# openSX70_ALADDIN_V396SEEED_20180210.net
KiCad netlist of a schematic drawn in EAGLE
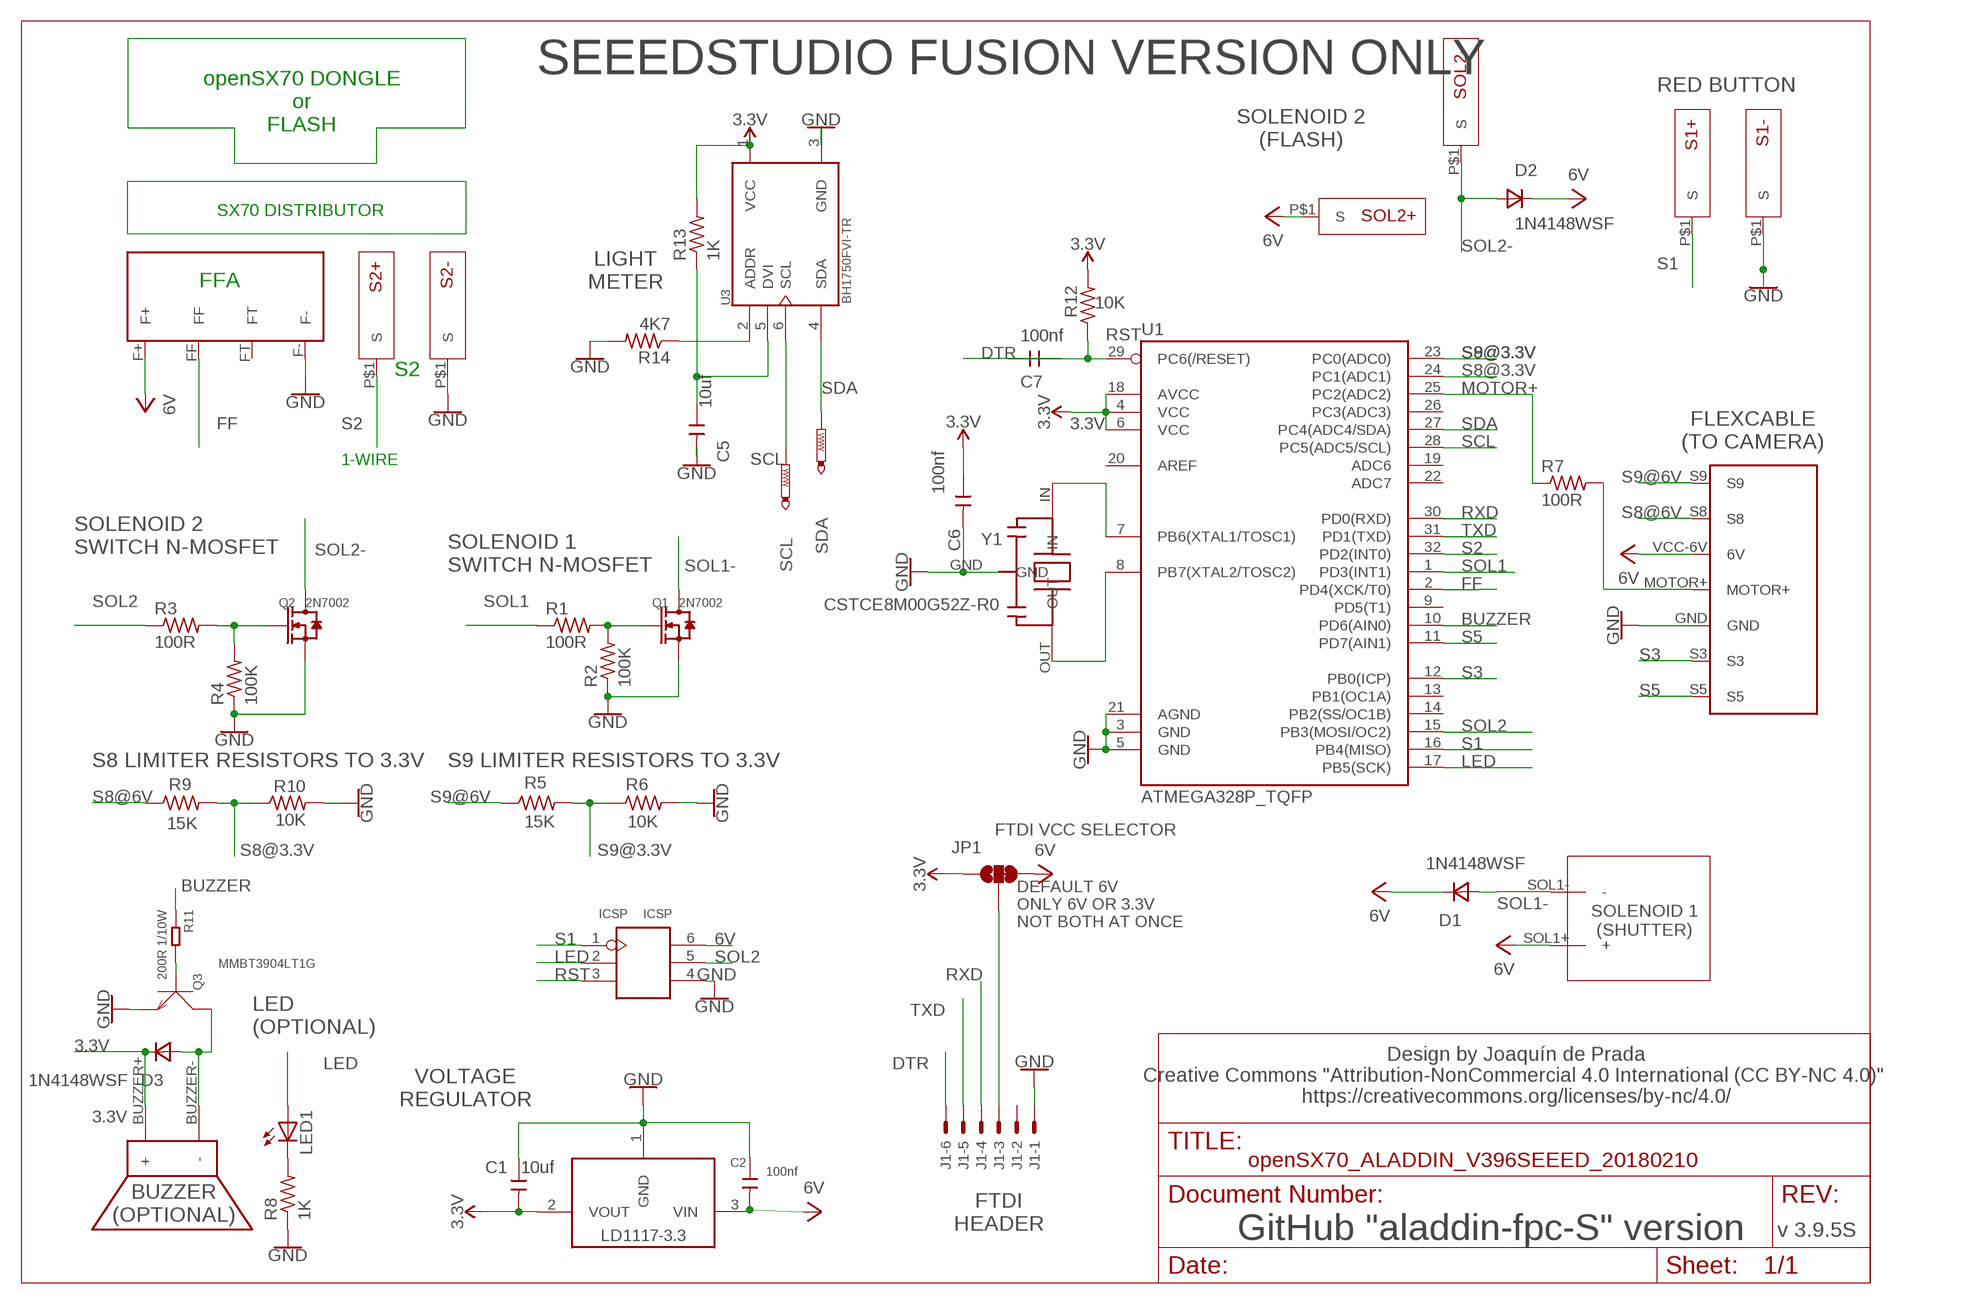
[diagram p0: schematic, sheet 1]

(export (version "E")
  (design (tool "Eeschema 10.0.6"))
  (components
    (comp (ref "C1")
      (value "10uf")
      (footprint "eagle-import:C0603")
      (fields (field (name "MPN") "CC0603KRX5R6BB106"))
      (libsource (lib "eagle-import") (part "CERAMIC-10UF-10V-10%-X5R(0603)"))
    )
    (comp (ref "C2")
      (value "100nf")
      (footprint "eagle-import:C0603")
      (fields (field (name "MPN") "CC0603KRX7R9BB104"))
      (libsource (lib "eagle-import") (part "CERAMIC-100NF-50V-10%-X7R(0603)"))
    )
    (comp (ref "C5")
      (value "10uf")
      (footprint "eagle-import:C0603")
      (fields (field (name "MPN") "CC0603KRX5R6BB106"))
      (libsource (lib "eagle-import") (part "CERAMIC-10UF-10V-10%-X5R(0603)"))
    )
    (comp (ref "C6")
      (value "100nf")
      (footprint "eagle-import:C0603")
      (fields (field (name "MPN") "CC0603KRX7R9BB104"))
      (libsource (lib "eagle-import") (part "CERAMIC-100NF-50V-10%-X7R(0603)"))
    )
    (comp (ref "C7")
      (value "100nf")
      (footprint "eagle-import:C0603")
      (fields (field (name "MPN") "CC0603KRX7R9BB104"))
      (libsource (lib "eagle-import") (part "CERAMIC-100NF-50V-10%-X7R(0603)"))
    )
    (comp (ref "D1")
      (value "1N4148WSF")
      (footprint "eagle-import:SOD323")
      (fields (field (name "MPN") "CDSOD323-T05C"))
      (libsource (lib "eagle-import") (part "DSOD323"))
    )
    (comp (ref "D2")
      (value "1N4148WSF")
      (footprint "eagle-import:SOD323")
      (fields (field (name "MPN") "CDSOD323-T05C"))
      (libsource (lib "eagle-import") (part "DSOD323"))
    )
    (comp (ref "D3")
      (value "1N4148WSF")
      (footprint "eagle-import:SOD323")
      (fields (field (name "MPN") "CDSOD323-T05C"))
      (libsource (lib "eagle-import") (part "DSOD323"))
    )
    (comp (ref "ICSP")
      (value "ICSP")
      (footprint "eagle-import:H2X3-2.54")
      (libsource (lib "eagle-import") (part "ICSP"))
    )
    (comp (ref "J1")
      (value "GND")
      (footprint "eagle-import:XF2L-0625-1")
      (fields (field (name "MF") "OMRON COMPONENTS USA") (field (name "MPN") "XF2L-0625-1"))
      (libsource (lib "eagle-import") (part "XF2-06?25-1L"))
    )
    (comp (ref "JP1")
      (value "FTDI VCC SELECTOR")
      (footprint "eagle-import:SMT-JUMPER_3_1-NC_TRACE_SILK")
      (libsource (lib "eagle-import") (part "JUMPER-SMT_3_1-NC_TRACE_SILK"))
    )
    (comp (ref "LD11172.5V")
      (value "LD1117 2.5V")
      (footprint "eagle-import:SOT223")
      (fields (field (name "MF") "Advanced Monolithic Systems") (field (name "MP") "AMS1117-5.0"))
      (libsource (lib "eagle-import") (part "LD1117-3.3"))
    )
    (comp (ref "LED1")
      (value "LEDCHIPLED_0805")
      (footprint "eagle-import:CHIPLED_0805")
      (libsource (lib "eagle-import") (part "LEDCHIPLED_0805"))
    )
    (comp (ref "Q1")
      (value "2N7002")
      (footprint "eagle-import:SOT-23")
      (fields (field (name "MPN") "2N7002,215"))
      (libsource (lib "eagle-import") (part "SMD-MOSFET-N-CH-60V-300MA-LOGIC-LEVEL-FET-2N7002(SOT-23)"))
    )
    (comp (ref "Q2")
      (value "2N7002")
      (footprint "eagle-import:SOT-23")
      (fields (field (name "MPN") "2N7002,215"))
      (libsource (lib "eagle-import") (part "SMD-MOSFET-N-CH-60V-300MA-LOGIC-LEVEL-FET-2N7002(SOT-23)"))
    )
    (comp (ref "Q3")
      (value "MMBT3904LT1G")
      (footprint "eagle-import:SOT-23")
      (libsource (lib "eagle-import") (part "SMD-TRANSISTORS-NPN-40V-200MA-MMBT3904LT1G(SOT-23)"))
    )
    (comp (ref "R1")
      (value "100R")
      (footprint "eagle-import:R0603")
      (libsource (lib "eagle-import") (part "R-US_R0603"))
    )
    (comp (ref "R2")
      (value "100K")
      (footprint "eagle-import:R0603")
      (libsource (lib "eagle-import") (part "R-US_R0603"))
    )
    (comp (ref "R3")
      (value "100R")
      (footprint "eagle-import:R0603")
      (libsource (lib "eagle-import") (part "R-US_R0603"))
    )
    (comp (ref "R4")
      (value "100K")
      (footprint "eagle-import:R0603")
      (libsource (lib "eagle-import") (part "R-US_R0603"))
    )
    (comp (ref "R5")
      (value "15K")
      (footprint "eagle-import:R0603")
      (libsource (lib "eagle-import") (part "R-US_R0603"))
    )
    (comp (ref "R6")
      (value "10K")
      (footprint "eagle-import:R0603")
      (libsource (lib "eagle-import") (part "R-US_R0603"))
    )
    (comp (ref "R7")
      (value "100R")
      (footprint "eagle-import:R0603")
      (libsource (lib "eagle-import") (part "R-US_R0603"))
    )
    (comp (ref "R8")
      (value "1K")
      (footprint "eagle-import:R0603")
      (libsource (lib "eagle-import") (part "R-US_R0603"))
    )
    (comp (ref "R9")
      (value "15K")
      (footprint "eagle-import:R0603")
      (libsource (lib "eagle-import") (part "R-US_R0603"))
    )
    (comp (ref "R10")
      (value "10K")
      (footprint "eagle-import:R0603")
      (libsource (lib "eagle-import") (part "R-US_R0603"))
    )
    (comp (ref "R11")
      (value "200R 1/10W")
      (footprint "eagle-import:R0603")
      (fields (field (name "MPN") "RC0603JR-07200RL"))
      (libsource (lib "eagle-import") (part "SMD-RES-200R-5%-1/10W(0603)"))
    )
    (comp (ref "R12")
      (value "10K")
      (footprint "eagle-import:R0603")
      (libsource (lib "eagle-import") (part "R-US_R0603"))
    )
    (comp (ref "R13")
      (value "1K")
      (footprint "eagle-import:R0603")
      (libsource (lib "eagle-import") (part "R-US_R0603"))
    )
    (comp (ref "R14")
      (value "4K7")
      (footprint "eagle-import:R0603")
      (libsource (lib "eagle-import") (part "R-US_R0603"))
    )
    (comp (ref "S1+")
      (value "SX70-S-PAD-NEW")
      (footprint "eagle-import:SX70-S-PAD2")
      (libsource (lib "eagle-import") (part "SX70-S-PAD-NEW"))
    )
    (comp (ref "S1-")
      (value "SX70-S-PAD-NEW")
      (footprint "eagle-import:SX70-S-PAD2")
      (libsource (lib "eagle-import") (part "SX70-S-PAD-NEW"))
    )
    (comp (ref "S2+")
      (value "SX70-S-PAD-NEW")
      (footprint "eagle-import:SX70-S-PAD2")
      (libsource (lib "eagle-import") (part "SX70-S-PAD-NEW"))
    )
    (comp (ref "S2-")
      (value "SX70-S-PAD-NEW")
      (footprint "eagle-import:SX70-S-PAD2")
      (libsource (lib "eagle-import") (part "SX70-S-PAD-NEW"))
    )
    (comp (ref "SCL")
      (value "PTR1TP08R")
      (footprint "eagle-import:TP08R")
      (libsource (lib "eagle-import") (part "PTR1TP08R"))
    )
    (comp (ref "SDA")
      (value "PTR1TP08R")
      (footprint "eagle-import:TP08R")
      (libsource (lib "eagle-import") (part "PTR1TP08R"))
    )
    (comp (ref "SOL1")
      (value "SX70-SOLENOID1-2PADS")
      (footprint "eagle-import:SX70-SOLENOID1-2")
      (libsource (lib "eagle-import") (part "SX70-SOLENOID1-2PADS"))
    )
    (comp (ref "SOL2+")
      (value "SX70-S-PAD-NEW")
      (footprint "eagle-import:SX70-S-PAD2")
      (libsource (lib "eagle-import") (part "SX70-S-PAD-NEW"))
    )
    (comp (ref "SOL2-")
      (value "SX70-S-PAD-NEW")
      (footprint "eagle-import:SX70-S-PAD2")
      (libsource (lib "eagle-import") (part "SX70-S-PAD-NEW"))
    )
    (comp (ref "U$1")
      (value "SX70-7-PAD")
      (footprint "eagle-import:SX70-7-PAD")
      (libsource (lib "eagle-import") (part "SX70-7-PAD"))
    )
    (comp (ref "U$2")
      (value "FFA")
      (footprint "eagle-import:FFA-PAD-PACKAGE")
      (libsource (lib "eagle-import") (part "SX70-FFA-PAD"))
    )
    (comp (ref "U$3")
      (value "CSET8-5G_V2")
      (footprint "eagle-import:CSET8-5G_PACKAGE")
      (libsource (lib "eagle-import") (part "CSET8-5G_V2"))
    )
    (comp (ref "U1")
      (value "ATMEGA328P_TQFP")
      (footprint "eagle-import:TQFP32-08")
      (libsource (lib "eagle-import") (part "ATMEGA328P_TQFP"))
    )
    (comp (ref "U3")
      (value "BH1750FVI-TR")
      (footprint "eagle-import:SOTFL50P300X75-6N")
      (fields (field (name "MF") "Rohm"))
      (libsource (lib "eagle-import") (part "BH1750FVI-TR"))
    )
    (comp (ref "Y1")
      (value "CSTCE8M00G52Z-R0")
      (footprint "eagle-import:CFP95P160X100-3N")
      (fields (field (name "MF") "Murata") (field (name "MP") "CSTCE16M0V53-R0"))
      (libsource (lib "eagle-import") (part "CSTCE16M0V53-R0"))
    )
  )
  (nets
    (net (code "1") (name "/BUZZER") (class "Default")
      (node (ref "R11") (pin "1") (pinfunction "1_1") (pintype "passive"))
      (node (ref "U1") (pin "10") (pinfunction "PD6(AIN0)_10") (pintype "bidirectional"))
    )
    (net (code "2") (name "/DTR") (class "Default")
      (node (ref "C7") (pin "1") (pinfunction "1_1") (pintype "passive"))
      (node (ref "J1") (pin "6") (pinfunction "MS_6") (pintype "passive"))
    )
    (net (code "3") (name "/FF") (class "Default")
      (node (ref "U$2") (pin "FF") (pinfunction "FF_FF") (pintype "bidirectional"))
      (node (ref "U1") (pin "2") (pinfunction "PD4(XCK/T0)_2") (pintype "bidirectional"))
    )
    (net (code "4") (name "/LED") (class "Default")
      (node (ref "ICSP") (pin "2") (pinfunction "SCK_2") (pintype "bidirectional"))
      (node (ref "LED1") (pin "A") (pinfunction "A_A") (pintype "passive"))
      (node (ref "U1") (pin "17") (pinfunction "PB5(SCK)_17") (pintype "bidirectional"))
    )
    (net (code "5") (name "/MOTOR+") (class "Default")
      (node (ref "R7") (pin "1") (pinfunction "1_1") (pintype "passive"))
      (node (ref "U1") (pin "25") (pinfunction "PC2(ADC2)_25") (pintype "bidirectional"))
    )
    (net (code "6") (name "/RST") (class "Default")
      (node (ref "C7") (pin "2") (pinfunction "2_2") (pintype "passive"))
      (node (ref "ICSP") (pin "3") (pinfunction "RST_3") (pintype "bidirectional"))
      (node (ref "R12") (pin "1") (pinfunction "1_1") (pintype "passive"))
      (node (ref "U1") (pin "29") (pinfunction "PC6(/RESET)_29") (pintype "bidirectional"))
    )
    (net (code "7") (name "/RXD") (class "Default")
      (node (ref "J1") (pin "4") (pinfunction "MS_4") (pintype "passive"))
      (node (ref "U1") (pin "30") (pinfunction "PD0(RXD)_30") (pintype "bidirectional"))
    )
    (net (code "8") (name "/S1") (class "Default")
      (node (ref "ICSP") (pin "1") (pinfunction "MISO_1") (pintype "bidirectional"))
      (node (ref "S1+") (pin "P$1") (pinfunction "S_P$1") (pintype "bidirectional"))
      (node (ref "U1") (pin "16") (pinfunction "PB4(MISO)_16") (pintype "bidirectional"))
    )
    (net (code "9") (name "/S2") (class "Default")
      (node (ref "S2+") (pin "P$1") (pinfunction "S_P$1") (pintype "bidirectional"))
      (node (ref "U1") (pin "32") (pinfunction "PD2(INT0)_32") (pintype "bidirectional"))
    )
    (net (code "10") (name "/S3") (class "Default")
      (node (ref "U$1") (pin "S3") (pinfunction "S3_S3") (pintype "bidirectional"))
      (node (ref "U1") (pin "12") (pinfunction "PB0(ICP)_12") (pintype "bidirectional"))
    )
    (net (code "11") (name "/S5") (class "Default")
      (node (ref "U$1") (pin "S5") (pinfunction "S5_S5") (pintype "bidirectional"))
      (node (ref "U1") (pin "11") (pinfunction "PD7(AIN1)_11") (pintype "bidirectional"))
    )
    (net (code "12") (name "/S8@3.3V") (class "Default")
      (node (ref "R10") (pin "1") (pinfunction "1_1") (pintype "passive"))
      (node (ref "R9") (pin "2") (pinfunction "2_2") (pintype "passive"))
      (node (ref "U1") (pin "24") (pinfunction "PC1(ADC1)_24") (pintype "bidirectional"))
    )
    (net (code "13") (name "/S8@6V") (class "Default")
      (node (ref "R9") (pin "1") (pinfunction "1_1") (pintype "passive"))
      (node (ref "U$1") (pin "S8") (pinfunction "S8_S8") (pintype "bidirectional"))
    )
    (net (code "14") (name "/S9@3.3V") (class "Default")
      (node (ref "R5") (pin "2") (pinfunction "2_2") (pintype "passive"))
      (node (ref "R6") (pin "1") (pinfunction "1_1") (pintype "passive"))
      (node (ref "U1") (pin "23") (pinfunction "PC0(ADC0)_23") (pintype "bidirectional"))
    )
    (net (code "15") (name "/S9@6V") (class "Default")
      (node (ref "R5") (pin "1") (pinfunction "1_1") (pintype "passive"))
      (node (ref "U$1") (pin "S9") (pinfunction "S9_S9") (pintype "bidirectional"))
    )
    (net (code "16") (name "/SCL") (class "Default")
      (node (ref "SCL") (pin "TP") (pinfunction "TP_TP") (pintype "input"))
      (node (ref "U1") (pin "28") (pinfunction "PC5(ADC5/SCL)_28") (pintype "bidirectional"))
      (node (ref "U3") (pin "6") (pinfunction "SCL_6") (pintype "input"))
    )
    (net (code "17") (name "/SDA") (class "Default")
      (node (ref "SDA") (pin "TP") (pinfunction "TP_TP") (pintype "input"))
      (node (ref "U1") (pin "27") (pinfunction "PC4(ADC4/SDA)_27") (pintype "bidirectional"))
      (node (ref "U3") (pin "4") (pinfunction "SDA_4") (pintype "bidirectional"))
    )
    (net (code "18") (name "/SOL1") (class "Default")
      (node (ref "R1") (pin "1") (pinfunction "1_1") (pintype "passive"))
      (node (ref "U1") (pin "1") (pinfunction "PD3(INT1)_1") (pintype "bidirectional"))
    )
    (net (code "19") (name "/SOL1-") (class "Default")
      (node (ref "D1") (pin "2") (pinfunction "A_2") (pintype "passive"))
      (node (ref "Q1") (pin "3") (pinfunction "D_3") (pintype "passive"))
      (node (ref "SOL1") (pin "SOL1-") (pinfunction "-_SOL1-") (pintype "bidirectional"))
    )
    (net (code "20") (name "/SOL2") (class "Default")
      (node (ref "ICSP") (pin "5") (pinfunction "MOSI_5") (pintype "bidirectional"))
      (node (ref "R3") (pin "1") (pinfunction "1_1") (pintype "passive"))
      (node (ref "U1") (pin "15") (pinfunction "PB3(MOSI/OC2)_15") (pintype "bidirectional"))
    )
    (net (code "21") (name "/SOL2-") (class "Default")
      (node (ref "D2") (pin "2") (pinfunction "A_2") (pintype "passive"))
      (node (ref "Q2") (pin "3") (pinfunction "D_3") (pintype "passive"))
      (node (ref "SOL2-") (pin "P$1") (pinfunction "S_P$1") (pintype "bidirectional"))
    )
    (net (code "22") (name "/TXD") (class "Default")
      (node (ref "J1") (pin "5") (pinfunction "MS_5") (pintype "passive"))
      (node (ref "U1") (pin "31") (pinfunction "PD1(TXD)_31") (pintype "bidirectional"))
    )
    (net (code "23") (name "3.3V") (class "Default")
      (node (ref "C1") (pin "2") (pinfunction "2_2") (pintype "passive"))
      (node (ref "C6") (pin "1") (pinfunction "1_1") (pintype "passive"))
      (node (ref "D3") (pin "1") (pinfunction "C_1") (pintype "passive"))
      (node (ref "JP1") (pin "1") (pinfunction "1_1") (pintype "passive"))
      (node (ref "LD11172.5V") (pin "2") (pinfunction "VOUT_2") (pintype "bidirectional"))
      (node (ref "R12") (pin "2") (pinfunction "2_2") (pintype "passive"))
      (node (ref "R13") (pin "2") (pinfunction "2_2") (pintype "passive"))
      (node (ref "U$3") (pin "BUZZER+") (pinfunction "+_BUZZER+") (pintype "bidirectional"))
      (node (ref "U1") (pin "18") (pinfunction "AVCC_18") (pintype "bidirectional"))
      (node (ref "U1") (pin "4") (pinfunction "VCC_4") (pintype "bidirectional"))
      (node (ref "U1") (pin "6") (pinfunction "VCC_6") (pintype "bidirectional"))
      (node (ref "U3") (pin "1") (pinfunction "VCC_1") (pintype "power_in"))
    )
    (net (code "24") (name "6V") (class "Default")
      (node (ref "C2") (pin "2") (pinfunction "2_2") (pintype "passive"))
      (node (ref "D1") (pin "1") (pinfunction "C_1") (pintype "passive"))
      (node (ref "D2") (pin "1") (pinfunction "C_1") (pintype "passive"))
      (node (ref "ICSP") (pin "6") (pinfunction "VCC_6") (pintype "bidirectional"))
      (node (ref "JP1") (pin "3") (pinfunction "3_3") (pintype "passive"))
      (node (ref "LD11172.5V") (pin "3") (pinfunction "VIN_3") (pintype "bidirectional"))
      (node (ref "SOL1") (pin "SOL1+") (pinfunction "+_SOL1+") (pintype "bidirectional"))
      (node (ref "SOL2+") (pin "P$1") (pinfunction "S_P$1") (pintype "bidirectional"))
      (node (ref "U$1") (pin "VCC-6V") (pinfunction "6V_VCC-6V") (pintype "bidirectional"))
      (node (ref "U$2") (pin "F+") (pinfunction "F+_F+") (pintype "bidirectional"))
    )
    (net (code "25") (name "GND") (class "Default")
      (node (ref "C1") (pin "1") (pinfunction "1_1") (pintype "passive"))
      (node (ref "C2") (pin "1") (pinfunction "1_1") (pintype "passive"))
      (node (ref "C5") (pin "2") (pinfunction "2_2") (pintype "passive"))
      (node (ref "C6") (pin "2") (pinfunction "2_2") (pintype "passive"))
      (node (ref "ICSP") (pin "4") (pinfunction "GND_4") (pintype "bidirectional"))
      (node (ref "J1") (pin "1") (pinfunction "MS_1") (pintype "passive"))
      (node (ref "LD11172.5V") (pin "1") (pinfunction "GND_1") (pintype "bidirectional"))
      (node (ref "Q1") (pin "2") (pinfunction "S_2") (pintype "passive"))
      (node (ref "Q2") (pin "2") (pinfunction "S_2") (pintype "passive"))
      (node (ref "Q3") (pin "2") (pinfunction "E_2") (pintype "passive"))
      (node (ref "R10") (pin "2") (pinfunction "2_2") (pintype "passive"))
      (node (ref "R14") (pin "2") (pinfunction "2_2") (pintype "passive"))
      (node (ref "R2") (pin "1") (pinfunction "1_1") (pintype "passive"))
      (node (ref "R4") (pin "1") (pinfunction "1_1") (pintype "passive"))
      (node (ref "R6") (pin "2") (pinfunction "2_2") (pintype "passive"))
      (node (ref "R8") (pin "1") (pinfunction "1_1") (pintype "passive"))
      (node (ref "S1-") (pin "P$1") (pinfunction "S_P$1") (pintype "bidirectional"))
      (node (ref "S2-") (pin "P$1") (pinfunction "S_P$1") (pintype "bidirectional"))
      (node (ref "U$1") (pin "GND") (pinfunction "GND_GND") (pintype "bidirectional"))
      (node (ref "U$2") (pin "F-") (pinfunction "F-_F-") (pintype "bidirectional"))
      (node (ref "U1") (pin "21") (pinfunction "AGND_21") (pintype "bidirectional"))
      (node (ref "U1") (pin "3") (pinfunction "GND_3") (pintype "bidirectional"))
      (node (ref "U1") (pin "5") (pinfunction "GND_5") (pintype "bidirectional"))
      (node (ref "U3") (pin "3") (pinfunction "GND_3") (pintype "power_in"))
      (node (ref "Y1") (pin "GND") (pinfunction "GND_GND") (pintype "passive"))
    )
    (net (code "26") (name "Net-(D3-A)") (class "Default")
      (node (ref "D3") (pin "2") (pinfunction "A_2") (pintype "passive"))
      (node (ref "Q3") (pin "3") (pinfunction "C_3") (pintype "passive"))
      (node (ref "U$3") (pin "BUZZER-") (pinfunction "-_BUZZER-") (pintype "bidirectional"))
    )
    (net (code "27") (name "Net-(J1C-MS)") (class "Default")
      (node (ref "J1") (pin "3") (pinfunction "MS_3") (pintype "passive"))
      (node (ref "JP1") (pin "2") (pinfunction "2_2") (pintype "passive"))
    )
    (net (code "28") (name "Net-(LED1-PadC)") (class "Default")
      (node (ref "LED1") (pin "C") (pinfunction "C_C") (pintype "passive"))
      (node (ref "R8") (pin "2") (pinfunction "2_2") (pintype "passive"))
    )
    (net (code "29") (name "Net-(Q1-G)") (class "Default")
      (node (ref "Q1") (pin "1") (pinfunction "G_1") (pintype "passive"))
      (node (ref "R1") (pin "2") (pinfunction "2_2") (pintype "passive"))
      (node (ref "R2") (pin "2") (pinfunction "2_2") (pintype "passive"))
    )
    (net (code "30") (name "Net-(Q2-G)") (class "Default")
      (node (ref "Q2") (pin "1") (pinfunction "G_1") (pintype "passive"))
      (node (ref "R3") (pin "2") (pinfunction "2_2") (pintype "passive"))
      (node (ref "R4") (pin "2") (pinfunction "2_2") (pintype "passive"))
    )
    (net (code "31") (name "Net-(Q3-B)") (class "Default")
      (node (ref "Q3") (pin "1") (pinfunction "B_1") (pintype "passive"))
      (node (ref "R11") (pin "2") (pinfunction "2_2") (pintype "passive"))
    )
    (net (code "32") (name "Net-(R7-Pad2)") (class "Default")
      (node (ref "R7") (pin "2") (pinfunction "2_2") (pintype "passive"))
      (node (ref "U$1") (pin "MOTOR+") (pinfunction "MOTOR+_MOTOR+") (pintype "bidirectional"))
    )
    (net (code "33") (name "Net-(U1-PB6(XTAL1{slash}TOSC1))") (class "Default")
      (node (ref "U1") (pin "7") (pinfunction "PB6(XTAL1/TOSC1)_7") (pintype "bidirectional"))
      (node (ref "Y1") (pin "IN") (pinfunction "IN_IN") (pintype "input"))
    )
    (net (code "34") (name "Net-(U1-PB7(XTAL2{slash}TOSC2))") (class "Default")
      (node (ref "U1") (pin "8") (pinfunction "PB7(XTAL2/TOSC2)_8") (pintype "bidirectional"))
      (node (ref "Y1") (pin "OUT") (pinfunction "OUT_OUT") (pintype "output"))
    )
    (net (code "35") (name "Net-(U3-ADDR)") (class "Default")
      (node (ref "R14") (pin "1") (pinfunction "1_1") (pintype "passive"))
      (node (ref "U3") (pin "2") (pinfunction "ADDR_2") (pintype "input"))
    )
    (net (code "36") (name "Net-(U3-DVI)") (class "Default")
      (node (ref "C5") (pin "1") (pinfunction "1_1") (pintype "passive"))
      (node (ref "R13") (pin "1") (pinfunction "1_1") (pintype "passive"))
      (node (ref "U3") (pin "5") (pinfunction "DVI_5") (pintype "input"))
    )
    (net (code "37") (name "unconnected-(J1B-MS-Pad2)") (class "Default")
      (node (ref "J1") (pin "2") (pinfunction "MS_2") (pintype "passive"))
    )
    (net (code "38") (name "unconnected-(U$2-PadFT)") (class "Default")
      (node (ref "U$2") (pin "FT") (pinfunction "FT_FT") (pintype "bidirectional"))
    )
    (net (code "39") (name "unconnected-(U1-ADC6-Pad19)") (class "Default")
      (node (ref "U1") (pin "19") (pinfunction "ADC6_19") (pintype "bidirectional"))
    )
    (net (code "40") (name "unconnected-(U1-ADC7-Pad22)") (class "Default")
      (node (ref "U1") (pin "22") (pinfunction "ADC7_22") (pintype "bidirectional"))
    )
    (net (code "41") (name "unconnected-(U1-AREF-Pad20)") (class "Default")
      (node (ref "U1") (pin "20") (pinfunction "AREF_20") (pintype "bidirectional"))
    )
    (net (code "42") (name "unconnected-(U1-PB1(OC1A)-Pad13)") (class "Default")
      (node (ref "U1") (pin "13") (pinfunction "PB1(OC1A)_13") (pintype "bidirectional"))
    )
    (net (code "43") (name "unconnected-(U1-PB2(SS{slash}OC1B)-Pad14)") (class "Default")
      (node (ref "U1") (pin "14") (pinfunction "PB2(SS/OC1B)_14") (pintype "bidirectional"))
    )
    (net (code "44") (name "unconnected-(U1-PC3(ADC3)-Pad26)") (class "Default")
      (node (ref "U1") (pin "26") (pinfunction "PC3(ADC3)_26") (pintype "bidirectional"))
    )
    (net (code "45") (name "unconnected-(U1-PD5(T1)-Pad9)") (class "Default")
      (node (ref "U1") (pin "9") (pinfunction "PD5(T1)_9") (pintype "bidirectional"))
    )
  )
)
